# F3-Hexa-Brushed-SIDE-USB.net
KiCad netlist of a schematic drawn in EAGLE
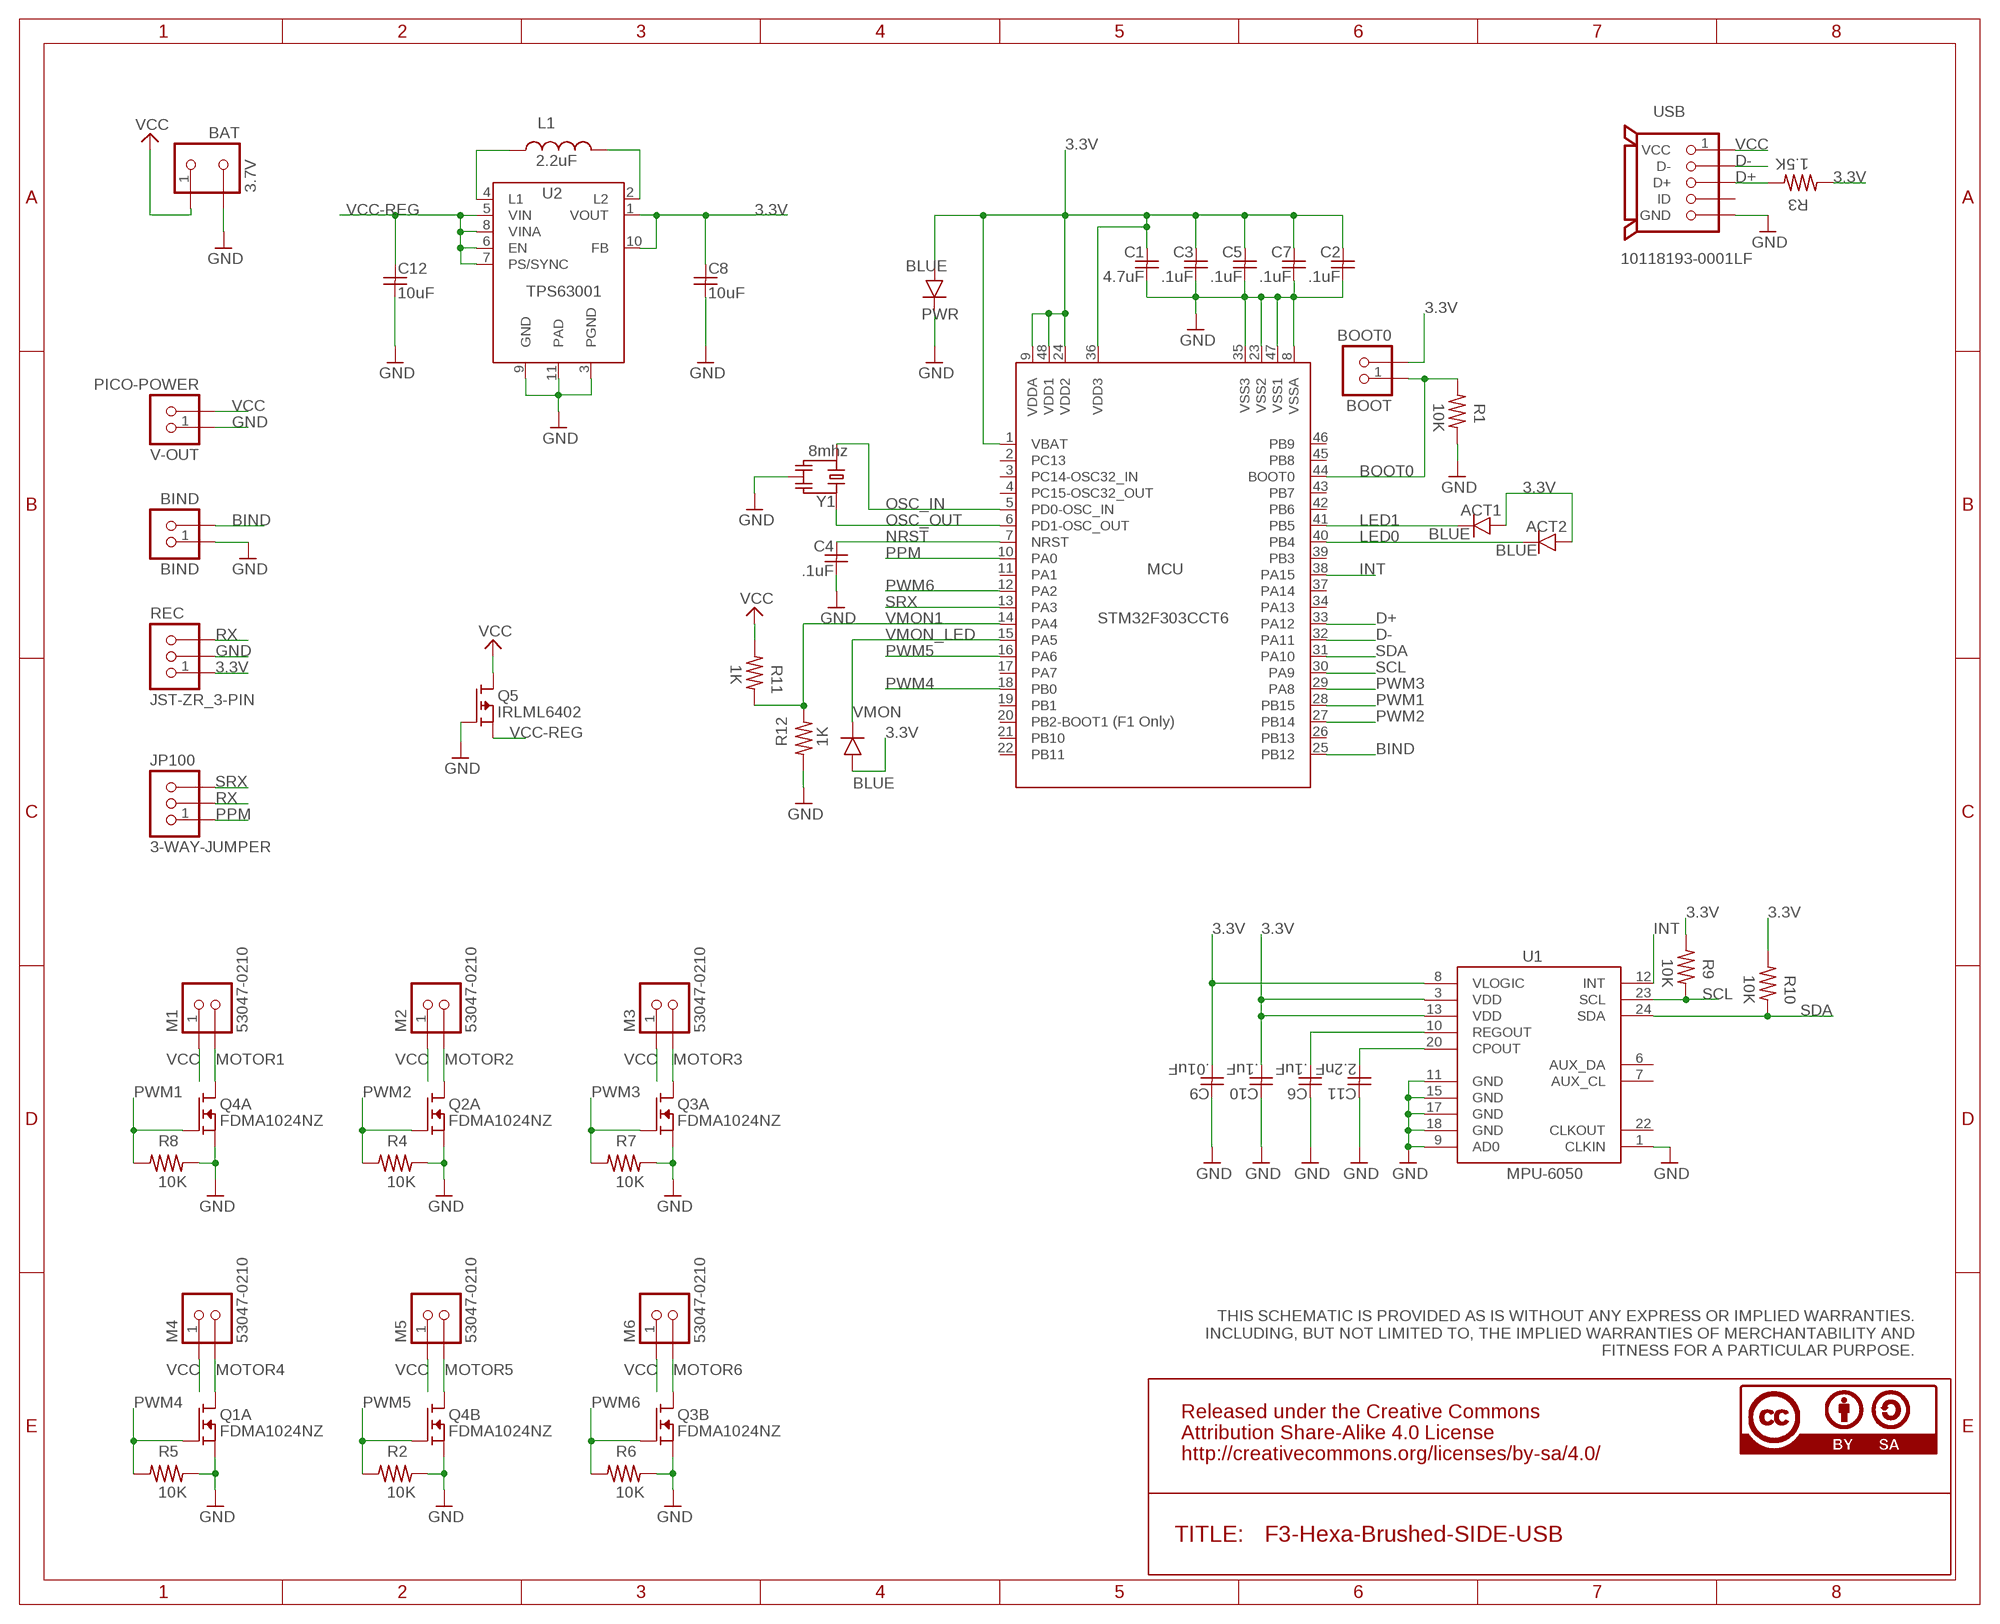
[diagram p0: schematic, sheet 1]

(export (version "E")
  (design (tool "Eeschema 10.0.6"))
  (components
    (comp (ref "ACT1")
      (value "BLUE")
      (footprint "eagle-import:SMD-CHIP-LED-0805")
      (fields (field (name "MF") "Kingbright") (field (name "MPN") "APHCM2012QBC/D-F01"))
      (libsource (lib "eagle-import") (part "SMD-CHIP-LED-0805"))
    )
    (comp (ref "ACT2")
      (value "BLUE")
      (footprint "eagle-import:SMD-CHIP-LED-0805")
      (fields (field (name "MF") "Kingbright") (field (name "MPN") "APHCM2012QBC/D-F01"))
      (libsource (lib "eagle-import") (part "SMD-CHIP-LED-0805"))
    )
    (comp (ref "BAT")
      (value "3.7V")
      (footprint "eagle-import:S2B-PH-K-S")
      (fields (field (name "MF") "JST") (field (name "MPN") "S2B-PH-K-S"))
      (libsource (lib "eagle-import") (part "JST-PH-BAT"))
    )
    (comp (ref "BIND")
      (value "BIND")
      (footprint "eagle-import:B3U-1000P(M)")
      (fields (field (name "MF") "Omron") (field (name "MPN") "B3U-1000P"))
      (libsource (lib "eagle-import") (part "TACTILE-SWITCH"))
    )
    (comp (ref "BOOT")
      (value "BOOT0")
      (footprint "eagle-import:B3U-1000P(M)")
      (fields (field (name "MF") "Omron") (field (name "MPN") "B3U-1000P"))
      (libsource (lib "eagle-import") (part "TACTILE-SWITCH"))
    )
    (comp (ref "C1")
      (value "4.7uF")
      (footprint "eagle-import:MUR-CAP-0603")
      (fields (field (name "MF") "Murata") (field (name "MPN") "GRJ188C70J475KE11D"))
      (libsource (lib "eagle-import") (part "CAPACITOR4.7UF"))
    )
    (comp (ref "C2")
      (value ".1uF")
      (footprint "eagle-import:MUR-CAP-0603")
      (fields (field (name "MF") "Murata") (field (name "MPN") "GRM188R71C104KA01D"))
      (libsource (lib "eagle-import") (part "CAPACITOR.1UF"))
    )
    (comp (ref "C3")
      (value ".1uF")
      (footprint "eagle-import:MUR-CAP-0603")
      (fields (field (name "MF") "Murata") (field (name "MPN") "GRM188R71C104KA01D"))
      (libsource (lib "eagle-import") (part "CAPACITOR.1UF"))
    )
    (comp (ref "C4")
      (value ".1uF")
      (footprint "eagle-import:MUR-CAP-0603")
      (fields (field (name "MF") "Murata") (field (name "MPN") "GRM188R71C104KA01D"))
      (libsource (lib "eagle-import") (part "CAPACITOR.1UF"))
    )
    (comp (ref "C5")
      (value ".1uF")
      (footprint "eagle-import:MUR-CAP-0603")
      (fields (field (name "MF") "Murata") (field (name "MPN") "GRM188R71C104KA01D"))
      (libsource (lib "eagle-import") (part "CAPACITOR.1UF"))
    )
    (comp (ref "C6")
      (value ".1uF")
      (footprint "eagle-import:MUR-CAP-0603")
      (fields (field (name "MF") "Murata") (field (name "MPN") "GRM188R71C104KA01D"))
      (libsource (lib "eagle-import") (part "CAPACITOR.1UF"))
    )
    (comp (ref "C7")
      (value ".1uF")
      (footprint "eagle-import:MUR-CAP-0603")
      (fields (field (name "MF") "Murata") (field (name "MPN") "GRM188R71C104KA01D"))
      (libsource (lib "eagle-import") (part "CAPACITOR.1UF"))
    )
    (comp (ref "C8")
      (value "10uF")
      (footprint "eagle-import:YUDEN-CAP-0805")
      (fields (field (name "MF") "Taiyo Yuden") (field (name "MPN") "JMK212AB7106KG-T"))
      (libsource (lib "eagle-import") (part "CAPACITOR10UF"))
    )
    (comp (ref "C9")
      (value ".01uF")
      (footprint "eagle-import:MUR-CAP-0603")
      (fields (field (name "MF") "Murata") (field (name "MPN") "GRM188R71C103KA01D"))
      (libsource (lib "eagle-import") (part "CAPACITOR.01UF"))
    )
    (comp (ref "C10")
      (value ".1uF")
      (footprint "eagle-import:MUR-CAP-0603")
      (fields (field (name "MF") "Murata") (field (name "MPN") "GRM188R71C104KA01D"))
      (libsource (lib "eagle-import") (part "CAPACITOR.1UF"))
    )
    (comp (ref "C11")
      (value "2.2nF")
      (footprint "eagle-import:MUR-CAP-0603")
      (fields (field (name "MF") "Murata") (field (name "MPN") "GRM188R71C222KA01D"))
      (libsource (lib "eagle-import") (part "CAPACITOR2.2NF"))
    )
    (comp (ref "C12")
      (value "10uF")
      (footprint "eagle-import:YUDEN-CAP-0805")
      (fields (field (name "MF") "Taiyo Yuden") (field (name "MPN") "JMK212AB7106KG-T"))
      (libsource (lib "eagle-import") (part "CAPACITOR10UF"))
    )
    (comp (ref "JP100")
      (value "3-WAY-JUMPER")
      (footprint "eagle-import:3-WAY-JUMPER")
      (libsource (lib "eagle-import") (part "3-WAY-JUMPER"))
    )
    (comp (ref "L1")
      (value "2.2uF")
      (footprint "eagle-import:NR301X")
      (fields (field (name "MF") "Taiyo Yuden") (field (name "MPN") "NR3015T2R2M"))
      (libsource (lib "eagle-import") (part "NR301X"))
    )
    (comp (ref "M1")
      (value "53047-0210")
      (footprint "eagle-import:PICO-53047-02")
      (fields (field (name "MF") "MOLEX"))
      (libsource (lib "eagle-import") (part "PICO-1.25-MOTOR"))
    )
    (comp (ref "M2")
      (value "53047-0210")
      (footprint "eagle-import:PICO-53047-02")
      (fields (field (name "MF") "MOLEX"))
      (libsource (lib "eagle-import") (part "PICO-1.25-MOTOR"))
    )
    (comp (ref "M3")
      (value "53047-0210")
      (footprint "eagle-import:PICO-53047-02")
      (fields (field (name "MF") "MOLEX"))
      (libsource (lib "eagle-import") (part "PICO-1.25-MOTOR"))
    )
    (comp (ref "M4")
      (value "53047-0210")
      (footprint "eagle-import:PICO-53047-02")
      (fields (field (name "MF") "MOLEX"))
      (libsource (lib "eagle-import") (part "PICO-1.25-MOTOR"))
    )
    (comp (ref "M5")
      (value "53047-0210")
      (footprint "eagle-import:PICO-53047-02")
      (fields (field (name "MF") "MOLEX"))
      (libsource (lib "eagle-import") (part "PICO-1.25-MOTOR"))
    )
    (comp (ref "M6")
      (value "53047-0210")
      (footprint "eagle-import:PICO-53047-02")
      (fields (field (name "MF") "MOLEX"))
      (libsource (lib "eagle-import") (part "PICO-1.25-MOTOR"))
    )
    (comp (ref "MCU")
      (value "STM32F303CCT6")
      (footprint "eagle-import:LQFP48-7X7")
      (fields (field (name "MF") "ST"))
      (libsource (lib "eagle-import") (part "STM32FX03-F3"))
    )
    (comp (ref "PWR")
      (value "BLUE")
      (footprint "eagle-import:SMD-CHIP-LED-0805")
      (fields (field (name "MF") "Kingbright") (field (name "MPN") "APHCM2012QBC/D-F01"))
      (libsource (lib "eagle-import") (part "SMD-CHIP-LED-0805"))
    )
    (comp (ref "Q1")
      (value "FDMA1024NZ")
      (footprint "eagle-import:MICROFET-2X2_DUAL")
      (fields (field (name "MF") "Fairchild"))
      (libsource (lib "eagle-import") (part "FDMA1024NZ"))
    )
    (comp (ref "Q2")
      (value "FDMA1024NZ")
      (footprint "eagle-import:MICROFET-2X2_DUAL")
      (fields (field (name "MF") "Fairchild"))
      (libsource (lib "eagle-import") (part "FDMA1024NZ"))
    )
    (comp (ref "Q3")
      (value "FDMA1024NZ")
      (footprint "eagle-import:MICROFET-2X2_DUAL")
      (fields (field (name "MF") "Fairchild"))
      (libsource (lib "eagle-import") (part "FDMA1024NZ"))
    )
    (comp (ref "Q4")
      (value "FDMA1024NZ")
      (footprint "eagle-import:MICROFET-2X2_DUAL")
      (fields (field (name "MF") "Fairchild"))
      (libsource (lib "eagle-import") (part "FDMA1024NZ"))
    )
    (comp (ref "Q5")
      (value "IRLML6402")
      (footprint "eagle-import:SOT-23")
      (fields (field (name "MF") "IR"))
      (libsource (lib "eagle-import") (part "MOSFET-P"))
    )
    (comp (ref "R1")
      (value "10K")
      (footprint "eagle-import:VISH-RES-0603")
      (fields (field (name "MF") "Vishay") (field (name "MPN") "CRCW060310K0FKEAHP"))
      (libsource (lib "eagle-import") (part "RESISTOR10K"))
    )
    (comp (ref "R2")
      (value "10K")
      (footprint "eagle-import:VISH-RES-0603")
      (fields (field (name "MF") "Vishay") (field (name "MPN") "CRCW060310K0FKEAHP"))
      (libsource (lib "eagle-import") (part "RESISTOR10K"))
    )
    (comp (ref "R3")
      (value "1.5K")
      (footprint "eagle-import:VISH-RES-0603")
      (fields (field (name "MF") "Vishay") (field (name "MPN") "CRCW06031K50FKEAHP"))
      (libsource (lib "eagle-import") (part "RESISTOR1.5K"))
    )
    (comp (ref "R4")
      (value "10K")
      (footprint "eagle-import:VISH-RES-0603")
      (fields (field (name "MF") "Vishay") (field (name "MPN") "CRCW060310K0FKEAHP"))
      (libsource (lib "eagle-import") (part "RESISTOR10K"))
    )
    (comp (ref "R5")
      (value "10K")
      (footprint "eagle-import:VISH-RES-0603")
      (fields (field (name "MF") "Vishay") (field (name "MPN") "CRCW060310K0FKEAHP"))
      (libsource (lib "eagle-import") (part "RESISTOR10K"))
    )
    (comp (ref "R6")
      (value "10K")
      (footprint "eagle-import:VISH-RES-0603")
      (fields (field (name "MF") "Vishay") (field (name "MPN") "CRCW060310K0FKEAHP"))
      (libsource (lib "eagle-import") (part "RESISTOR10K"))
    )
    (comp (ref "R7")
      (value "10K")
      (footprint "eagle-import:VISH-RES-0603")
      (fields (field (name "MF") "Vishay") (field (name "MPN") "CRCW060310K0FKEAHP"))
      (libsource (lib "eagle-import") (part "RESISTOR10K"))
    )
    (comp (ref "R8")
      (value "10K")
      (footprint "eagle-import:VISH-RES-0603")
      (fields (field (name "MF") "Vishay") (field (name "MPN") "CRCW060310K0FKEAHP"))
      (libsource (lib "eagle-import") (part "RESISTOR10K"))
    )
    (comp (ref "R9")
      (value "10K")
      (footprint "eagle-import:VISH-RES-0603")
      (fields (field (name "MF") "Vishay") (field (name "MPN") "CRCW060310K0FKEAHP"))
      (libsource (lib "eagle-import") (part "RESISTOR10K"))
    )
    (comp (ref "R10")
      (value "10K")
      (footprint "eagle-import:VISH-RES-0603")
      (fields (field (name "MF") "Vishay") (field (name "MPN") "CRCW060310K0FKEAHP"))
      (libsource (lib "eagle-import") (part "RESISTOR10K"))
    )
    (comp (ref "R11")
      (value "1K")
      (footprint "eagle-import:VISH-RES-0603")
      (fields (field (name "MF") "Vishay") (field (name "MPN") "CRCW06031K00FKEAHP"))
      (libsource (lib "eagle-import") (part "RESISTOR1K"))
    )
    (comp (ref "R12")
      (value "1K")
      (footprint "eagle-import:VISH-RES-0603")
      (fields (field (name "MF") "Vishay") (field (name "MPN") "CRCW06031K00FKEAHP"))
      (libsource (lib "eagle-import") (part "RESISTOR1K"))
    )
    (comp (ref "REC")
      (value "JST-ZR_3-PIN")
      (footprint "eagle-import:S3B-ZR")
      (fields (field (name "MF") "JST") (field (name "MPN") "S3B-ZR"))
      (libsource (lib "eagle-import") (part "JST-ZR_3-PIN"))
    )
    (comp (ref "U1")
      (value "MPU-6050")
      (footprint "eagle-import:QFN24-4X4")
      (fields (field (name "MF") "Invensense"))
      (libsource (lib "eagle-import") (part "MPU-6050"))
    )
    (comp (ref "U2")
      (value "TPS63001")
      (footprint "eagle-import:VSON-N10")
      (fields (field (name "MF") "TI") (field (name "MPN") "TPS63001DRCR"))
      (libsource (lib "eagle-import") (part "TPS630XX-TPS63001"))
    )
    (comp (ref "USB")
      (value "10118193-0001LF")
      (footprint "eagle-import:10118193-0001LF")
      (fields (field (name "MF") "FCI"))
      (libsource (lib "eagle-import") (part "USB-MICRO-B-FCI"))
    )
    (comp (ref "V-OUT")
      (value "PICO-POWER")
      (footprint "eagle-import:PICO_1.25_.5MM")
      (fields (field (name "MF") "Molex") (field (name "MPN") "53047-0210"))
      (libsource (lib "eagle-import") (part "PICO-POWER"))
    )
    (comp (ref "VMON")
      (value "BLUE")
      (footprint "eagle-import:SMD-CHIP-LED-0805")
      (fields (field (name "MF") "Kingbright") (field (name "MPN") "APHCM2012QBC/D-F01"))
      (libsource (lib "eagle-import") (part "SMD-CHIP-LED-0805"))
    )
    (comp (ref "Y1")
      (value "8mhz")
      (footprint "eagle-import:RESONATOR_8")
      (fields (field (name "MF") "Murata") (field (name "MPN") "CSTCE8M00G55-R0"))
      (libsource (lib "eagle-import") (part "RESONATOR8MHZ"))
    )
  )
  (nets
    (net (code "1") (name "/3.3V") (class "Default")
      (node (ref "ACT1") (pin "A") (pinfunction "A_A") (pintype "passive"))
      (node (ref "ACT2") (pin "A") (pinfunction "A_A") (pintype "passive"))
      (node (ref "BOOT") (pin "2") (pinfunction "2_2") (pintype "passive"))
      (node (ref "C1") (pin "1") (pinfunction "1_1") (pintype "passive"))
      (node (ref "C10") (pin "2") (pinfunction "2_2") (pintype "passive"))
      (node (ref "C2") (pin "1") (pinfunction "1_1") (pintype "passive"))
      (node (ref "C3") (pin "1") (pinfunction "1_1") (pintype "passive"))
      (node (ref "C5") (pin "1") (pinfunction "1_1") (pintype "passive"))
      (node (ref "C7") (pin "1") (pinfunction "1_1") (pintype "passive"))
      (node (ref "C8") (pin "1") (pinfunction "1_1") (pintype "passive"))
      (node (ref "C9") (pin "2") (pinfunction "2_2") (pintype "passive"))
      (node (ref "MCU") (pin "1") (pinfunction "VBAT_1") (pintype "bidirectional"))
      (node (ref "MCU") (pin "24") (pinfunction "VDD2_24") (pintype "bidirectional"))
      (node (ref "MCU") (pin "36") (pinfunction "VDD3_36") (pintype "bidirectional"))
      (node (ref "MCU") (pin "48") (pinfunction "VDD1_48") (pintype "bidirectional"))
      (node (ref "MCU") (pin "9") (pinfunction "VDDA_9") (pintype "bidirectional"))
      (node (ref "PWR") (pin "A") (pinfunction "A_A") (pintype "passive"))
      (node (ref "R10") (pin "2") (pinfunction "2_2") (pintype "passive"))
      (node (ref "R3") (pin "2") (pinfunction "2_2") (pintype "passive"))
      (node (ref "R9") (pin "2") (pinfunction "2_2") (pintype "passive"))
      (node (ref "REC") (pin "1") (pinfunction "1_1") (pintype "bidirectional"))
      (node (ref "U1") (pin "13") (pinfunction "VDD_13") (pintype "bidirectional"))
      (node (ref "U1") (pin "3") (pinfunction "VDD_3") (pintype "bidirectional"))
      (node (ref "U1") (pin "8") (pinfunction "VLOGIC_8") (pintype "bidirectional"))
      (node (ref "U2") (pin "1") (pinfunction "VOUT_1") (pintype "bidirectional"))
      (node (ref "U2") (pin "10") (pinfunction "FB_10") (pintype "bidirectional"))
      (node (ref "VMON") (pin "A") (pinfunction "A_A") (pintype "passive"))
    )
    (net (code "2") (name "/BIND") (class "Default")
      (node (ref "BIND") (pin "2") (pinfunction "2_2") (pintype "passive"))
      (node (ref "MCU") (pin "25") (pinfunction "PB12_25") (pintype "bidirectional"))
    )
    (net (code "3") (name "/BOOT0") (class "Default")
      (node (ref "BOOT") (pin "1") (pinfunction "1_1") (pintype "passive"))
      (node (ref "MCU") (pin "44") (pinfunction "BOOT0_44") (pintype "bidirectional"))
      (node (ref "R1") (pin "2") (pinfunction "2_2") (pintype "passive"))
    )
    (net (code "4") (name "/D+") (class "Default")
      (node (ref "MCU") (pin "33") (pinfunction "PA12_33") (pintype "bidirectional"))
      (node (ref "R3") (pin "1") (pinfunction "1_1") (pintype "passive"))
      (node (ref "USB") (pin "3") (pinfunction "D+_3") (pintype "passive"))
    )
    (net (code "5") (name "/D-") (class "Default")
      (node (ref "MCU") (pin "32") (pinfunction "PA11_32") (pintype "bidirectional"))
      (node (ref "USB") (pin "2") (pinfunction "D-_2") (pintype "passive"))
    )
    (net (code "6") (name "/INT") (class "Default")
      (node (ref "MCU") (pin "38") (pinfunction "PA15_38") (pintype "bidirectional"))
      (node (ref "U1") (pin "12") (pinfunction "INT_12") (pintype "bidirectional"))
    )
    (net (code "7") (name "/LED0") (class "Default")
      (node (ref "ACT2") (pin "C") (pinfunction "C_C") (pintype "passive"))
      (node (ref "MCU") (pin "40") (pinfunction "PB4_40") (pintype "bidirectional"))
    )
    (net (code "8") (name "/LED1") (class "Default")
      (node (ref "ACT1") (pin "C") (pinfunction "C_C") (pintype "passive"))
      (node (ref "MCU") (pin "41") (pinfunction "PB5_41") (pintype "bidirectional"))
    )
    (net (code "9") (name "/MOTOR1") (class "Default")
      (node (ref "M1") (pin "2") (pinfunction "2_2") (pintype "passive"))
      (node (ref "Q4") (pin "A.D") (pinfunction "D_A.D") (pintype "bidirectional"))
      (node (ref "Q4") (pin "A.D1") (pinfunction "D_A.D1") (pintype "bidirectional"))
    )
    (net (code "10") (name "/MOTOR2") (class "Default")
      (node (ref "M2") (pin "2") (pinfunction "2_2") (pintype "passive"))
      (node (ref "Q2") (pin "A.D") (pinfunction "D_A.D") (pintype "bidirectional"))
      (node (ref "Q2") (pin "A.D1") (pinfunction "D_A.D1") (pintype "bidirectional"))
    )
    (net (code "11") (name "/MOTOR3") (class "Default")
      (node (ref "M3") (pin "2") (pinfunction "2_2") (pintype "passive"))
      (node (ref "Q3") (pin "A.D") (pinfunction "D_A.D") (pintype "bidirectional"))
      (node (ref "Q3") (pin "A.D1") (pinfunction "D_A.D1") (pintype "bidirectional"))
    )
    (net (code "12") (name "/MOTOR4") (class "Default")
      (node (ref "M4") (pin "2") (pinfunction "2_2") (pintype "passive"))
      (node (ref "Q1") (pin "A.D") (pinfunction "D_A.D") (pintype "bidirectional"))
      (node (ref "Q1") (pin "A.D1") (pinfunction "D_A.D1") (pintype "bidirectional"))
    )
    (net (code "13") (name "/MOTOR5") (class "Default")
      (node (ref "M5") (pin "2") (pinfunction "2_2") (pintype "passive"))
      (node (ref "Q4") (pin "B.D") (pinfunction "D_B.D") (pintype "bidirectional"))
      (node (ref "Q4") (pin "B.D1") (pinfunction "D_B.D1") (pintype "bidirectional"))
    )
    (net (code "14") (name "/MOTOR6") (class "Default")
      (node (ref "M6") (pin "2") (pinfunction "2_2") (pintype "passive"))
      (node (ref "Q3") (pin "B.D") (pinfunction "D_B.D") (pintype "bidirectional"))
      (node (ref "Q3") (pin "B.D1") (pinfunction "D_B.D1") (pintype "bidirectional"))
    )
    (net (code "15") (name "/NRST") (class "Default")
      (node (ref "C4") (pin "1") (pinfunction "1_1") (pintype "passive"))
      (node (ref "MCU") (pin "7") (pinfunction "NRST_7") (pintype "bidirectional"))
    )
    (net (code "16") (name "/OSC_IN") (class "Default")
      (node (ref "MCU") (pin "5") (pinfunction "PD0-OSC_IN_5") (pintype "bidirectional"))
      (node (ref "Y1") (pin "3") (pinfunction "3_3") (pintype "passive"))
    )
    (net (code "17") (name "/OSC_OUT") (class "Default")
      (node (ref "MCU") (pin "6") (pinfunction "PD1-OSC_OUT_6") (pintype "bidirectional"))
      (node (ref "Y1") (pin "1") (pinfunction "1_1") (pintype "passive"))
    )
    (net (code "18") (name "/PPM") (class "Default")
      (node (ref "JP100") (pin "1") (pinfunction "1_1") (pintype "bidirectional"))
      (node (ref "MCU") (pin "10") (pinfunction "PA0_10") (pintype "bidirectional"))
    )
    (net (code "19") (name "/PWM1") (class "Default")
      (node (ref "MCU") (pin "28") (pinfunction "PB15_28") (pintype "bidirectional"))
      (node (ref "Q4") (pin "A.G") (pinfunction "G_A.G") (pintype "bidirectional"))
      (node (ref "R8") (pin "2") (pinfunction "2_2") (pintype "passive"))
    )
    (net (code "20") (name "/PWM2") (class "Default")
      (node (ref "MCU") (pin "27") (pinfunction "PB14_27") (pintype "bidirectional"))
      (node (ref "Q2") (pin "A.G") (pinfunction "G_A.G") (pintype "bidirectional"))
      (node (ref "R4") (pin "2") (pinfunction "2_2") (pintype "passive"))
    )
    (net (code "21") (name "/PWM3") (class "Default")
      (node (ref "MCU") (pin "29") (pinfunction "PA8_29") (pintype "bidirectional"))
      (node (ref "Q3") (pin "A.G") (pinfunction "G_A.G") (pintype "bidirectional"))
      (node (ref "R7") (pin "2") (pinfunction "2_2") (pintype "passive"))
    )
    (net (code "22") (name "/PWM4") (class "Default")
      (node (ref "MCU") (pin "18") (pinfunction "PB0_18") (pintype "bidirectional"))
      (node (ref "Q1") (pin "A.G") (pinfunction "G_A.G") (pintype "bidirectional"))
      (node (ref "R5") (pin "2") (pinfunction "2_2") (pintype "passive"))
    )
    (net (code "23") (name "/PWM5") (class "Default")
      (node (ref "MCU") (pin "16") (pinfunction "PA6_16") (pintype "bidirectional"))
      (node (ref "Q4") (pin "B.G") (pinfunction "G_B.G") (pintype "bidirectional"))
      (node (ref "R2") (pin "2") (pinfunction "2_2") (pintype "passive"))
    )
    (net (code "24") (name "/PWM6") (class "Default")
      (node (ref "MCU") (pin "12") (pinfunction "PA2_12") (pintype "bidirectional"))
      (node (ref "Q3") (pin "B.G") (pinfunction "G_B.G") (pintype "bidirectional"))
      (node (ref "R6") (pin "2") (pinfunction "2_2") (pintype "passive"))
    )
    (net (code "25") (name "/RX") (class "Default")
      (node (ref "JP100") (pin "2") (pinfunction "2_2") (pintype "bidirectional"))
      (node (ref "REC") (pin "3") (pinfunction "3_3") (pintype "bidirectional"))
    )
    (net (code "26") (name "/SCL") (class "Default")
      (node (ref "MCU") (pin "30") (pinfunction "PA9_30") (pintype "bidirectional"))
      (node (ref "R9") (pin "1") (pinfunction "1_1") (pintype "passive"))
      (node (ref "U1") (pin "23") (pinfunction "SCL_23") (pintype "bidirectional"))
    )
    (net (code "27") (name "/SDA") (class "Default")
      (node (ref "MCU") (pin "31") (pinfunction "PA10_31") (pintype "bidirectional"))
      (node (ref "R10") (pin "1") (pinfunction "1_1") (pintype "passive"))
      (node (ref "U1") (pin "24") (pinfunction "SDA_24") (pintype "bidirectional"))
    )
    (net (code "28") (name "/SRX") (class "Default")
      (node (ref "JP100") (pin "3") (pinfunction "3_3") (pintype "bidirectional"))
      (node (ref "MCU") (pin "13") (pinfunction "PA3_13") (pintype "bidirectional"))
    )
    (net (code "29") (name "/VCC-REG") (class "Default")
      (node (ref "C12") (pin "1") (pinfunction "1_1") (pintype "passive"))
      (node (ref "Q5") (pin "2") (pinfunction "S_2") (pintype "bidirectional"))
      (node (ref "U2") (pin "5") (pinfunction "VIN_5") (pintype "bidirectional"))
      (node (ref "U2") (pin "6") (pinfunction "EN_6") (pintype "bidirectional"))
      (node (ref "U2") (pin "7") (pinfunction "PS/SYNC_7") (pintype "bidirectional"))
      (node (ref "U2") (pin "8") (pinfunction "VINA_8") (pintype "bidirectional"))
    )
    (net (code "30") (name "/VMON1") (class "Default")
      (node (ref "MCU") (pin "14") (pinfunction "PA4_14") (pintype "bidirectional"))
      (node (ref "R11") (pin "1") (pinfunction "1_1") (pintype "passive"))
      (node (ref "R12") (pin "1") (pinfunction "1_1") (pintype "passive"))
    )
    (net (code "31") (name "/VMON_LED") (class "Default")
      (node (ref "MCU") (pin "15") (pinfunction "PA5_15") (pintype "bidirectional"))
      (node (ref "VMON") (pin "C") (pinfunction "C_C") (pintype "passive"))
    )
    (net (code "32") (name "GND") (class "Default")
      (node (ref "BAT") (pin "2") (pinfunction "2_2") (pintype "bidirectional"))
      (node (ref "BIND") (pin "1") (pinfunction "1_1") (pintype "passive"))
      (node (ref "C1") (pin "2") (pinfunction "2_2") (pintype "passive"))
      (node (ref "C10") (pin "1") (pinfunction "1_1") (pintype "passive"))
      (node (ref "C11") (pin "1") (pinfunction "1_1") (pintype "passive"))
      (node (ref "C12") (pin "2") (pinfunction "2_2") (pintype "passive"))
      (node (ref "C2") (pin "2") (pinfunction "2_2") (pintype "passive"))
      (node (ref "C3") (pin "2") (pinfunction "2_2") (pintype "passive"))
      (node (ref "C4") (pin "2") (pinfunction "2_2") (pintype "passive"))
      (node (ref "C5") (pin "2") (pinfunction "2_2") (pintype "passive"))
      (node (ref "C6") (pin "1") (pinfunction "1_1") (pintype "passive"))
      (node (ref "C7") (pin "2") (pinfunction "2_2") (pintype "passive"))
      (node (ref "C8") (pin "2") (pinfunction "2_2") (pintype "passive"))
      (node (ref "C9") (pin "1") (pinfunction "1_1") (pintype "passive"))
      (node (ref "MCU") (pin "23") (pinfunction "VSS2_23") (pintype "bidirectional"))
      (node (ref "MCU") (pin "35") (pinfunction "VSS3_35") (pintype "bidirectional"))
      (node (ref "MCU") (pin "47") (pinfunction "VSS1_47") (pintype "bidirectional"))
      (node (ref "MCU") (pin "8") (pinfunction "VSSA_8") (pintype "bidirectional"))
      (node (ref "PWR") (pin "C") (pinfunction "C_C") (pintype "passive"))
      (node (ref "Q1") (pin "A.S") (pinfunction "S_A.S") (pintype "bidirectional"))
      (node (ref "Q2") (pin "A.S") (pinfunction "S_A.S") (pintype "bidirectional"))
      (node (ref "Q3") (pin "A.S") (pinfunction "S_A.S") (pintype "bidirectional"))
      (node (ref "Q3") (pin "B.S") (pinfunction "S_B.S") (pintype "bidirectional"))
      (node (ref "Q4") (pin "A.S") (pinfunction "S_A.S") (pintype "bidirectional"))
      (node (ref "Q4") (pin "B.S") (pinfunction "S_B.S") (pintype "bidirectional"))
      (node (ref "Q5") (pin "1") (pinfunction "G_1") (pintype "bidirectional"))
      (node (ref "R1") (pin "1") (pinfunction "1_1") (pintype "passive"))
      (node (ref "R12") (pin "2") (pinfunction "2_2") (pintype "passive"))
      (node (ref "R2") (pin "1") (pinfunction "1_1") (pintype "passive"))
      (node (ref "R4") (pin "1") (pinfunction "1_1") (pintype "passive"))
      (node (ref "R5") (pin "1") (pinfunction "1_1") (pintype "passive"))
      (node (ref "R6") (pin "1") (pinfunction "1_1") (pintype "passive"))
      (node (ref "R7") (pin "1") (pinfunction "1_1") (pintype "passive"))
      (node (ref "R8") (pin "1") (pinfunction "1_1") (pintype "passive"))
      (node (ref "REC") (pin "2") (pinfunction "2_2") (pintype "bidirectional"))
      (node (ref "U1") (pin "1") (pinfunction "CLKIN_1") (pintype "bidirectional"))
      (node (ref "U1") (pin "11") (pinfunction "GND_11") (pintype "bidirectional"))
      (node (ref "U1") (pin "15") (pinfunction "GND_15") (pintype "bidirectional"))
      (node (ref "U1") (pin "17") (pinfunction "GND_17") (pintype "bidirectional"))
      (node (ref "U1") (pin "18") (pinfunction "GND_18") (pintype "bidirectional"))
      (node (ref "U1") (pin "9") (pinfunction "AD0_9") (pintype "bidirectional"))
      (node (ref "U2") (pin "11") (pinfunction "PAD_11") (pintype "bidirectional"))
      (node (ref "U2") (pin "3") (pinfunction "PGND_3") (pintype "bidirectional"))
      (node (ref "U2") (pin "9") (pinfunction "GND_9") (pintype "bidirectional"))
      (node (ref "USB") (pin "5") (pinfunction "GND_5") (pintype "passive"))
      (node (ref "USB") (pin "GND") (pinfunction "GND_GND") (pintype "passive"))
      (node (ref "USB") (pin "GND2") (pinfunction "GND_GND2") (pintype "passive"))
      (node (ref "USB") (pin "HOLE1") (pinfunction "GND_HOLE1") (pintype "passive"))
      (node (ref "USB") (pin "HOLE2") (pinfunction "GND_HOLE2") (pintype "passive"))
      (node (ref "V-OUT") (pin "1") (pinfunction "1_1") (pintype "passive"))
      (node (ref "Y1") (pin "2") (pinfunction "2_2") (pintype "passive"))
    )
    (net (code "33") (name "Net-(U1-CPOUT)") (class "Default")
      (node (ref "C11") (pin "2") (pinfunction "2_2") (pintype "passive"))
      (node (ref "U1") (pin "20") (pinfunction "CPOUT_20") (pintype "bidirectional"))
    )
    (net (code "34") (name "Net-(U1-REGOUT)") (class "Default")
      (node (ref "C6") (pin "2") (pinfunction "2_2") (pintype "passive"))
      (node (ref "U1") (pin "10") (pinfunction "REGOUT_10") (pintype "bidirectional"))
    )
    (net (code "35") (name "Net-(U2-L1)") (class "Default")
      (node (ref "L1") (pin "1") (pinfunction "1_1") (pintype "passive"))
      (node (ref "U2") (pin "4") (pinfunction "L1_4") (pintype "bidirectional"))
    )
    (net (code "36") (name "Net-(U2-L2)") (class "Default")
      (node (ref "L1") (pin "2") (pinfunction "2_2") (pintype "passive"))
      (node (ref "U2") (pin "2") (pinfunction "L2_2") (pintype "bidirectional"))
    )
    (net (code "37") (name "VCC") (class "Default")
      (node (ref "BAT") (pin "1") (pinfunction "1_1") (pintype "bidirectional"))
      (node (ref "M1") (pin "1") (pinfunction "1_1") (pintype "passive"))
      (node (ref "M2") (pin "1") (pinfunction "1_1") (pintype "passive"))
      (node (ref "M3") (pin "1") (pinfunction "1_1") (pintype "passive"))
      (node (ref "M4") (pin "1") (pinfunction "1_1") (pintype "passive"))
      (node (ref "M5") (pin "1") (pinfunction "1_1") (pintype "passive"))
      (node (ref "M6") (pin "1") (pinfunction "1_1") (pintype "passive"))
      (node (ref "Q5") (pin "3") (pinfunction "D_3") (pintype "bidirectional"))
      (node (ref "R11") (pin "2") (pinfunction "2_2") (pintype "passive"))
      (node (ref "USB") (pin "1") (pinfunction "VCC_1") (pintype "passive"))
      (node (ref "V-OUT") (pin "2") (pinfunction "2_2") (pintype "passive"))
    )
    (net (code "38") (name "unconnected-(MCU-PA1-Pad11)") (class "Default")
      (node (ref "MCU") (pin "11") (pinfunction "PA1_11") (pintype "bidirectional"))
    )
    (net (code "39") (name "unconnected-(MCU-PA7-Pad17)") (class "Default")
      (node (ref "MCU") (pin "17") (pinfunction "PA7_17") (pintype "bidirectional"))
    )
    (net (code "40") (name "unconnected-(MCU-PA13-Pad34)") (class "Default")
      (node (ref "MCU") (pin "34") (pinfunction "PA13_34") (pintype "bidirectional"))
    )
    (net (code "41") (name "unconnected-(MCU-PA14-Pad37)") (class "Default")
      (node (ref "MCU") (pin "37") (pinfunction "PA14_37") (pintype "bidirectional"))
    )
    (net (code "42") (name "unconnected-(MCU-PB1-Pad19)") (class "Default")
      (node (ref "MCU") (pin "19") (pinfunction "PB1_19") (pintype "bidirectional"))
    )
    (net (code "43") (name "unconnected-(MCU-PB2-BOOT1-Pad20)") (class "Default")
      (node (ref "MCU") (pin "20") (pinfunction "PB2-BOOT1_20") (pintype "bidirectional"))
    )
    (net (code "44") (name "unconnected-(MCU-PB3-Pad39)") (class "Default")
      (node (ref "MCU") (pin "39") (pinfunction "PB3_39") (pintype "bidirectional"))
    )
    (net (code "45") (name "unconnected-(MCU-PB6-Pad42)") (class "Default")
      (node (ref "MCU") (pin "42") (pinfunction "PB6_42") (pintype "bidirectional"))
    )
    (net (code "46") (name "unconnected-(MCU-PB7-Pad43)") (class "Default")
      (node (ref "MCU") (pin "43") (pinfunction "PB7_43") (pintype "bidirectional"))
    )
    (net (code "47") (name "unconnected-(MCU-PB8-Pad45)") (class "Default")
      (node (ref "MCU") (pin "45") (pinfunction "PB8_45") (pintype "bidirectional"))
    )
    (net (code "48") (name "unconnected-(MCU-PB9-Pad46)") (class "Default")
      (node (ref "MCU") (pin "46") (pinfunction "PB9_46") (pintype "bidirectional"))
    )
    (net (code "49") (name "unconnected-(MCU-PB10-Pad21)") (class "Default")
      (node (ref "MCU") (pin "21") (pinfunction "PB10_21") (pintype "bidirectional"))
    )
    (net (code "50") (name "unconnected-(MCU-PB11-Pad22)") (class "Default")
      (node (ref "MCU") (pin "22") (pinfunction "PB11_22") (pintype "bidirectional"))
    )
    (net (code "51") (name "unconnected-(MCU-PB13-Pad26)") (class "Default")
      (node (ref "MCU") (pin "26") (pinfunction "PB13_26") (pintype "bidirectional"))
    )
    (net (code "52") (name "unconnected-(MCU-PC13-Pad2)") (class "Default")
      (node (ref "MCU") (pin "2") (pinfunction "PC13_2") (pintype "bidirectional"))
    )
    (net (code "53") (name "unconnected-(MCU-PC14-OSC32_IN-Pad3)") (class "Default")
      (node (ref "MCU") (pin "3") (pinfunction "PC14-OSC32_IN_3") (pintype "bidirectional"))
    )
    (net (code "54") (name "unconnected-(MCU-PC15-OSC32_OUT-Pad4)") (class "Default")
      (node (ref "MCU") (pin "4") (pinfunction "PC15-OSC32_OUT_4") (pintype "bidirectional"))
    )
    (net (code "55") (name "unconnected-(U1-AUX_CL-Pad7)") (class "Default")
      (node (ref "U1") (pin "7") (pinfunction "AUX_CL_7") (pintype "bidirectional"))
    )
    (net (code "56") (name "unconnected-(U1-AUX_DA-Pad6)") (class "Default")
      (node (ref "U1") (pin "6") (pinfunction "AUX_DA_6") (pintype "bidirectional"))
    )
    (net (code "57") (name "unconnected-(U1-CLKOUT-Pad22)") (class "Default")
      (node (ref "U1") (pin "22") (pinfunction "CLKOUT_22") (pintype "bidirectional"))
    )
    (net (code "58") (name "unconnected-(USB-ID-Pad4)") (class "Default")
      (node (ref "USB") (pin "4") (pinfunction "ID_4") (pintype "passive"))
    )
  )
)
